# expLoRaBLE_Thing_Plus.net
KiCad netlist of a schematic drawn in EAGLE
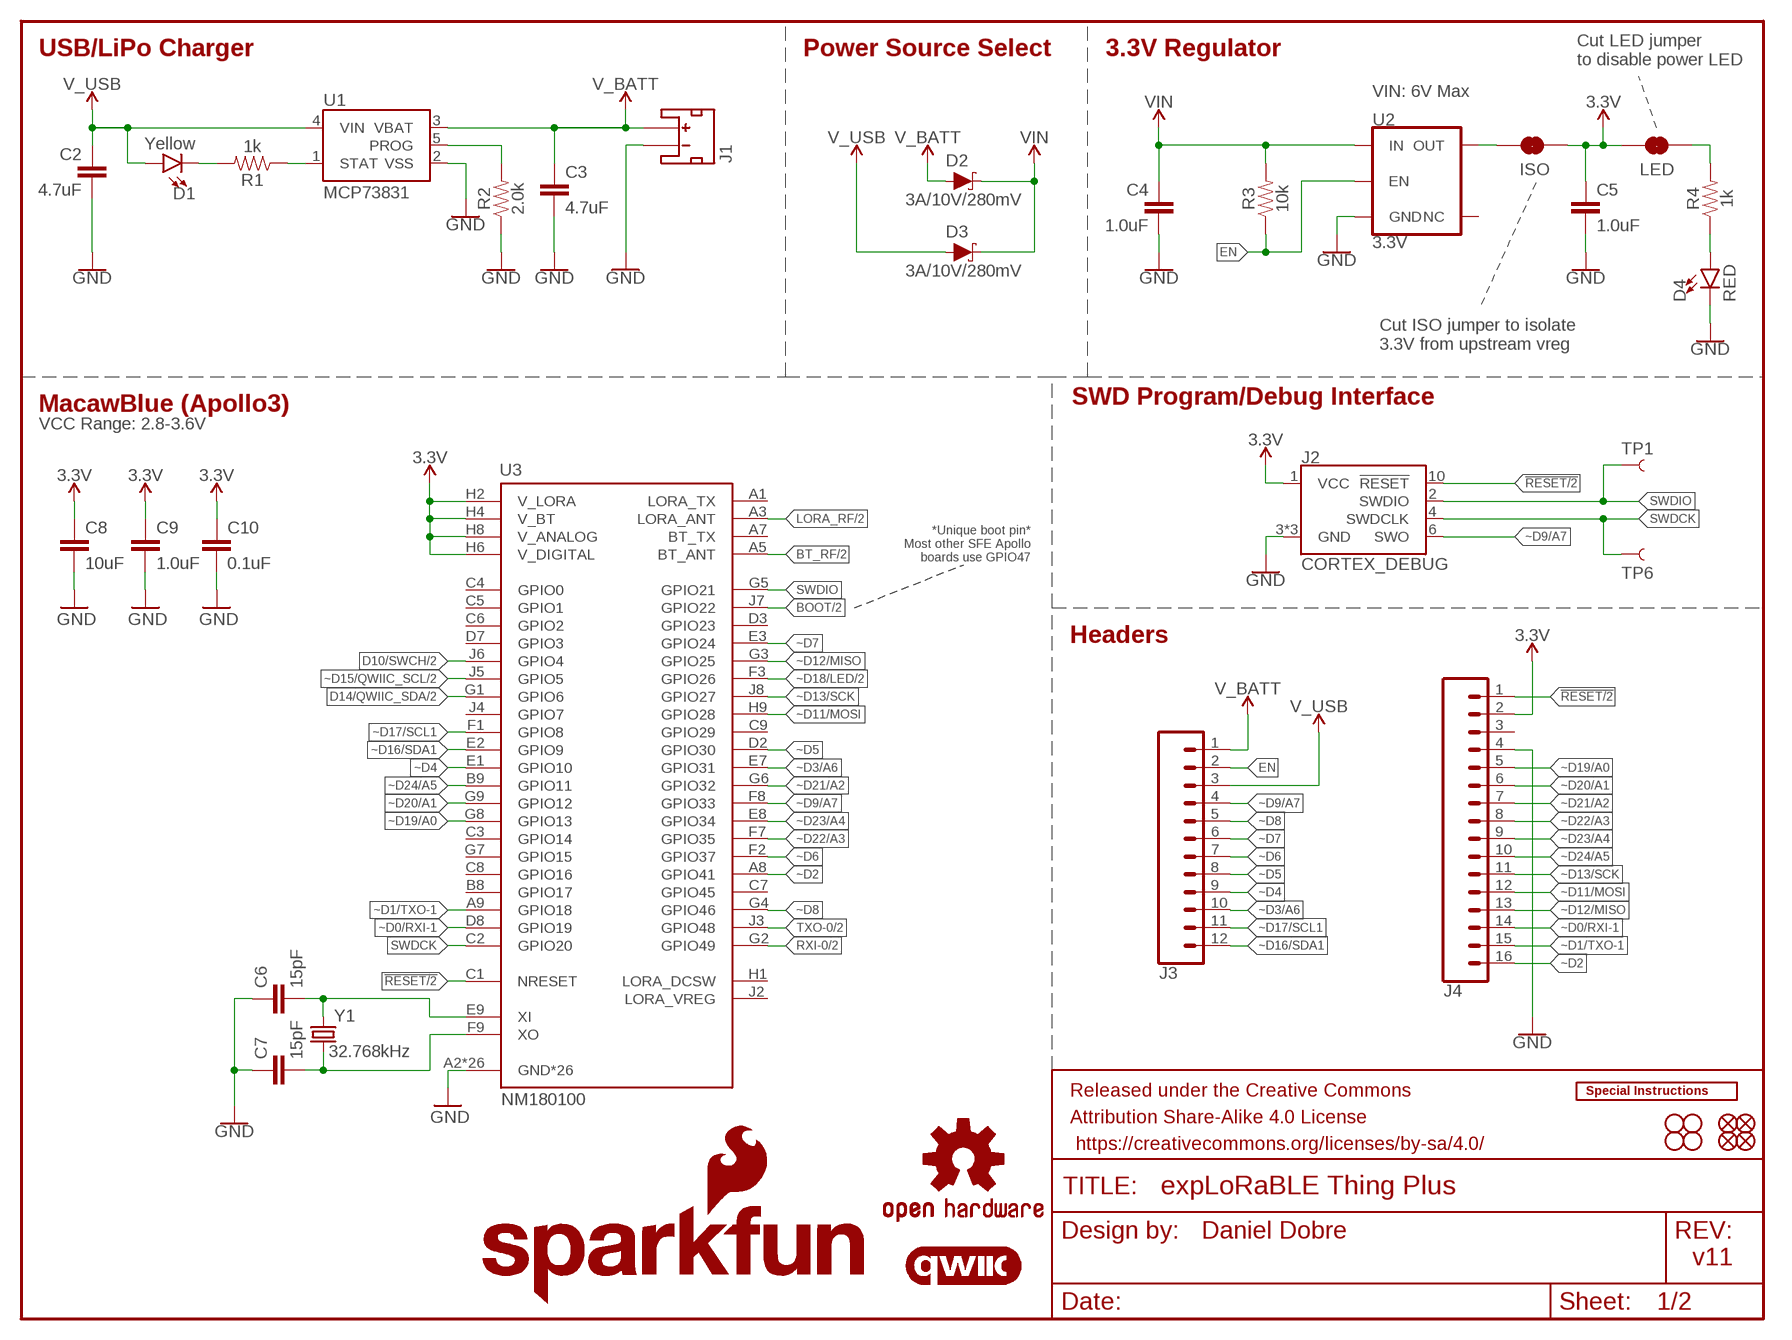
[diagram p0: schematic, sheet 1]
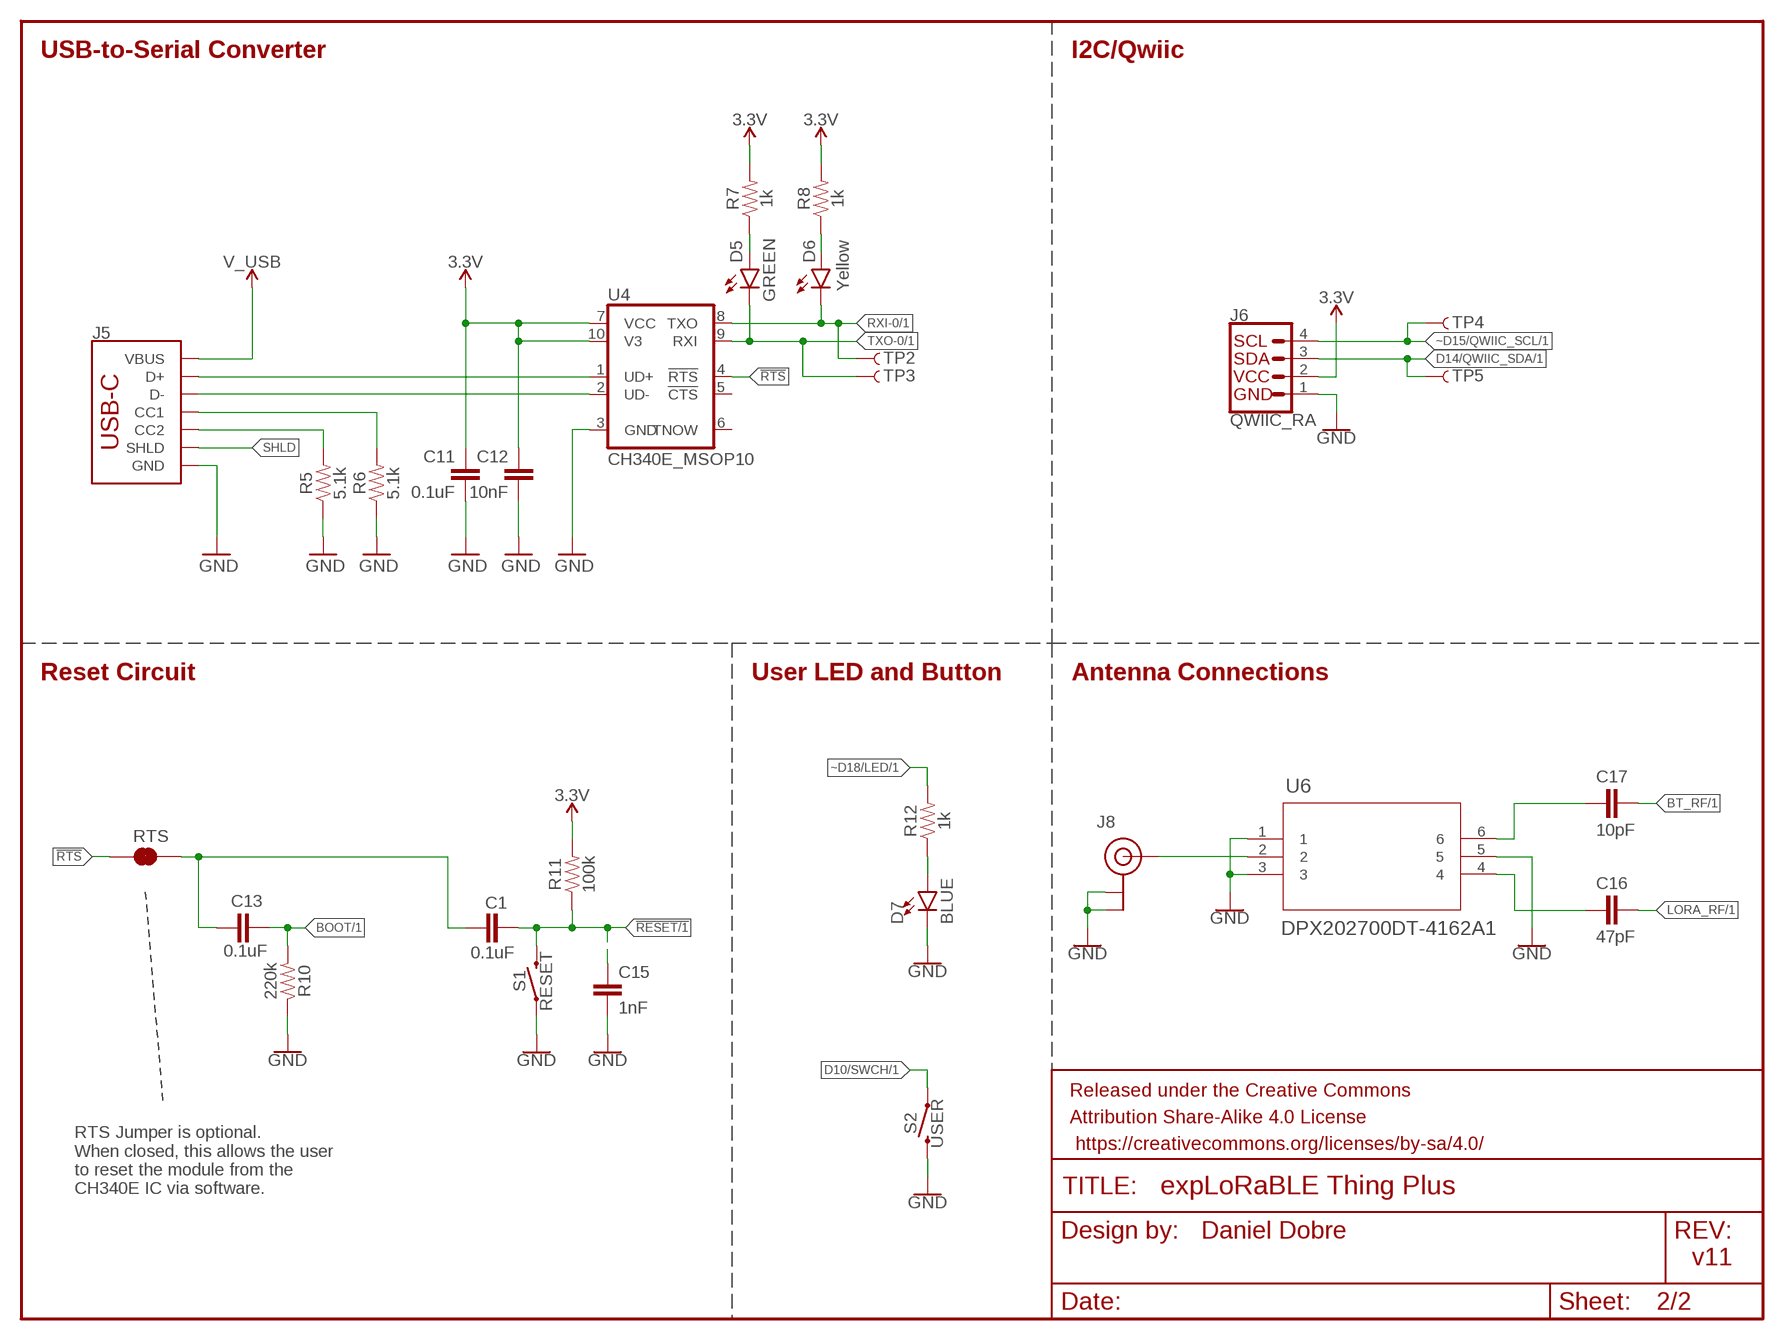
[diagram p1: schematic, sheet 2]

(export (version "E")
  (design (tool "Eeschema 10.0.6"))
  (components
    (comp (ref "C1")
      (value "0.1uF")
      (footprint "eagle-import:0603")
      (libsource (lib "eagle-import") (part "SparkFun-Capacitors_510_0.1UF-0603-25V-(+80/-20%)"))
    )
    (comp (ref "C11")
      (value "0.1uF")
      (footprint "eagle-import:0603")
      (libsource (lib "eagle-import") (part "SparkFun-Capacitors_23925113_0.1UF-0603-25V-(+80/-20%)"))
    )
    (comp (ref "C12")
      (value "10nF")
      (footprint "eagle-import:0603")
      (libsource (lib "eagle-import") (part "10NF-0603-50V-10%"))
    )
    (comp (ref "C13")
      (value "0.1uF")
      (footprint "eagle-import:0603")
      (libsource (lib "eagle-import") (part "0.1UF-0603-25V-(+80/-20%)"))
    )
    (comp (ref "C15")
      (value "1nF")
      (footprint "eagle-import:0603")
      (libsource (lib "eagle-import") (part "1.0NF/1000PF-0603-50V-10%"))
    )
    (comp (ref "C16")
      (value "47pF")
      (footprint "eagle-import:0603")
      (libsource (lib "eagle-import") (part "47PF-0603-50V-5%"))
    )
    (comp (ref "C17")
      (value "10pF")
      (footprint "eagle-import:0603")
      (libsource (lib "eagle-import") (part "10PF-0603-50V-5%"))
    )
    (comp (ref "D5")
      (value "GREEN")
      (footprint "eagle-import:LED-0603")
      (libsource (lib "eagle-import") (part "LED-GREEN0603"))
    )
    (comp (ref "D6")
      (value "Yellow")
      (footprint "eagle-import:LED-0603")
      (libsource (lib "eagle-import") (part "LED-YELLOW0603"))
    )
    (comp (ref "D7")
      (value "BLUE")
      (footprint "eagle-import:LED-0603")
      (libsource (lib "eagle-import") (part "LED-BLUE0603"))
    )
    (comp (ref "FRAME2")
      (value "FRAME-LETTERNO_PACKAGE")
      (footprint "eagle-import:DUMMY")
      (fields (field (name "DESIGNER") "Nobody"))
      (libsource (lib "eagle-import") (part "FRAME-LETTERNO_PACKAGE"))
    )
    (comp (ref "J5")
      (value "USB Female Type C Connector")
      (footprint "eagle-import:USB-C-16P-4LAYER-ISOLATED")
      (libsource (lib "eagle-import") (part "USB_C_4-LAYER-ISOLATED"))
    )
    (comp (ref "J6")
      (value "QWIIC_RA")
      (footprint "eagle-import:JST04_1MM_RA")
      (libsource (lib "eagle-import") (part "QWIIC_CONNECTORJS-1MM"))
    )
    (comp (ref "J8")
      (value "U.FL")
      (footprint "eagle-import:U.FL")
      (libsource (lib "eagle-import") (part "U.FL"))
    )
    (comp (ref "R5")
      (value "5.1k")
      (footprint "eagle-import:0603")
      (libsource (lib "eagle-import") (part "5.1KOHM5.1KOHM-0603-1/10W-1%"))
    )
    (comp (ref "R6")
      (value "5.1k")
      (footprint "eagle-import:0603")
      (libsource (lib "eagle-import") (part "5.1KOHM5.1KOHM-0603-1/10W-1%"))
    )
    (comp (ref "R7")
      (value "1k")
      (footprint "eagle-import:0603")
      (libsource (lib "eagle-import") (part "1KOHM-0603-1/10W-1%"))
    )
    (comp (ref "R8")
      (value "1k")
      (footprint "eagle-import:0603")
      (libsource (lib "eagle-import") (part "1KOHM-0603-1/10W-1%"))
    )
    (comp (ref "R10")
      (value "220k")
      (footprint "eagle-import:0603")
      (libsource (lib "eagle-import") (part "220KOHM-0603-1/10W-1%"))
    )
    (comp (ref "R11")
      (value "100k")
      (footprint "eagle-import:0603")
      (libsource (lib "eagle-import") (part "100KOHM-0603-1/10W-1%"))
    )
    (comp (ref "R12")
      (value "1k")
      (footprint "eagle-import:0603")
      (libsource (lib "eagle-import") (part "1KOHM-0603-1/10W-1%"))
    )
    (comp (ref "RTS")
      (value "JUMPER-SMT_2_NC_TRACE_SILK")
      (footprint "eagle-import:SMT-JUMPER_2_NC_TRACE_SILK")
      (libsource (lib "eagle-import") (part "JUMPER-SMT_2_NC_TRACE_SILK"))
    )
    (comp (ref "S1")
      (value "RESET")
      (footprint "eagle-import:TACTILE_SWITCH_SMD_4.6X2.8MM")
      (libsource (lib "eagle-import") (part "MOMENTARY-SWITCH-SPST-SMD-4.6X2.8MM"))
    )
    (comp (ref "S2")
      (value "USER")
      (footprint "eagle-import:TACTILE_SWITCH_SMD_4.6X2.8MM")
      (libsource (lib "eagle-import") (part "MOMENTARY-SWITCH-SPST-SMD-4.6X2.8MM"))
    )
    (comp (ref "TP2")
      (value "TEST-POINTTP_15TH_THRU")
      (footprint "eagle-import:TP_15TH")
      (libsource (lib "eagle-import") (part "TEST-POINTTP_15TH_THRU"))
    )
    (comp (ref "TP3")
      (value "TEST-POINTTP_15TH_THRU")
      (footprint "eagle-import:TP_15TH")
      (libsource (lib "eagle-import") (part "TEST-POINTTP_15TH_THRU"))
    )
    (comp (ref "TP4")
      (value "TEST-POINTTP_15TH_THRU")
      (footprint "eagle-import:TP_15TH")
      (libsource (lib "eagle-import") (part "TEST-POINTTP_15TH_THRU"))
    )
    (comp (ref "TP5")
      (value "TEST-POINTTP_15TH_THRU")
      (footprint "eagle-import:TP_15TH")
      (libsource (lib "eagle-import") (part "TEST-POINTTP_15TH_THRU"))
    )
    (comp (ref "U4")
      (value "CH340E_MSOP10")
      (footprint "eagle-import:MSOP10")
      (libsource (lib "eagle-import") (part "CH340E_MSOP10"))
    )
    (comp (ref "U6")
      (value "DPX202700DT-4162A1")
      (footprint "eagle-import:RF_4060A1_TDK")
      (fields (field (name "COPYRIGHT") "Copyright (C) 2018 Accelerated Designs. All rights reserved"))
      (libsource (lib "eagle-import") (part "DPX202700DT-4162A1"))
    )
    (comp (ref "C2")
      (value "4.7uF")
      (footprint "eagle-import:0603")
      (libsource (lib "eagle-import") (part "4.7UF-0603-6.3V-(10%)"))
    )
    (comp (ref "C3")
      (value "4.7uF")
      (footprint "eagle-import:0603")
      (libsource (lib "eagle-import") (part "4.7UF-0603-6.3V-(10%)"))
    )
    (comp (ref "C4")
      (value "1.0uF")
      (footprint "eagle-import:0603")
      (libsource (lib "eagle-import") (part "1.0UF-0603-16V-10%"))
    )
    (comp (ref "C5")
      (value "1.0uF")
      (footprint "eagle-import:0603")
      (libsource (lib "eagle-import") (part "1.0UF-0603-16V-10%"))
    )
    (comp (ref "C6")
      (value "15pF")
      (footprint "eagle-import:0603")
      (libsource (lib "eagle-import") (part "15PF-0603-50V-5%"))
    )
    (comp (ref "C7")
      (value "15pF")
      (footprint "eagle-import:0603")
      (libsource (lib "eagle-import") (part "15PF-0603-50V-5%"))
    )
    (comp (ref "C8")
      (value "10uF")
      (footprint "eagle-import:0603")
      (libsource (lib "eagle-import") (part "10UF-0603-6.3V-20%"))
    )
    (comp (ref "C9")
      (value "1.0uF")
      (footprint "eagle-import:0603")
      (libsource (lib "eagle-import") (part "1.0UF-0603-16V-10%"))
    )
    (comp (ref "C10")
      (value "0.1uF")
      (footprint "eagle-import:0603")
      (libsource (lib "eagle-import") (part "SparkFun-Capacitors_23925113_0.1UF-0603-25V-(+80/-20%)"))
    )
    (comp (ref "D1")
      (value "Yellow")
      (footprint "eagle-import:LED-0603")
      (libsource (lib "eagle-import") (part "LED-YELLOW0603"))
    )
    (comp (ref "D2")
      (value "3A/10V/280mV")
      (footprint "eagle-import:SOD-323")
      (libsource (lib "eagle-import") (part "DIODE-SCHOTTKY-BAT60A"))
    )
    (comp (ref "D3")
      (value "3A/10V/280mV")
      (footprint "eagle-import:SOD-323")
      (libsource (lib "eagle-import") (part "DIODE-SCHOTTKY-BAT60A"))
    )
    (comp (ref "D4")
      (value "RED")
      (footprint "eagle-import:LED-0603")
      (libsource (lib "eagle-import") (part "LED-RED0603"))
    )
    (comp (ref "FD1")
      (value "FIDUCIALUFIDUCIAL")
      (footprint "eagle-import:FIDUCIAL-MICRO")
      (libsource (lib "eagle-import") (part "FIDUCIALUFIDUCIAL"))
    )
    (comp (ref "FD2")
      (value "FIDUCIALUFIDUCIAL")
      (footprint "eagle-import:FIDUCIAL-MICRO")
      (libsource (lib "eagle-import") (part "FIDUCIALUFIDUCIAL"))
    )
    (comp (ref "FD3")
      (value "FIDUCIALUFIDUCIAL")
      (footprint "eagle-import:FIDUCIAL-MICRO")
      (libsource (lib "eagle-import") (part "FIDUCIALUFIDUCIAL"))
    )
    (comp (ref "FD4")
      (value "FIDUCIALUFIDUCIAL")
      (footprint "eagle-import:FIDUCIAL-MICRO")
      (libsource (lib "eagle-import") (part "FIDUCIALUFIDUCIAL"))
    )
    (comp (ref "FRAME1")
      (value "FRAME-LETTER")
      (footprint "eagle-import:CREATIVE_COMMONS")
      (libsource (lib "eagle-import") (part "FRAME-LETTER"))
    )
    (comp (ref "H1")
      (value "STAND-OFF")
      (footprint "eagle-import:STAND-OFF")
      (libsource (lib "eagle-import") (part "STAND-OFF"))
    )
    (comp (ref "H2")
      (value "STAND-OFF")
      (footprint "eagle-import:STAND-OFF")
      (libsource (lib "eagle-import") (part "STAND-OFF"))
    )
    (comp (ref "H3")
      (value "STAND-OFF")
      (footprint "eagle-import:STAND-OFF")
      (libsource (lib "eagle-import") (part "STAND-OFF"))
    )
    (comp (ref "H4")
      (value "STAND-OFF")
      (footprint "eagle-import:STAND-OFF")
      (libsource (lib "eagle-import") (part "STAND-OFF"))
    )
    (comp (ref "ISO")
      (value "JUMPER-SMT_2_NC_TRACE_SILK")
      (footprint "eagle-import:SMT-JUMPER_2_NC_TRACE_SILK")
      (libsource (lib "eagle-import") (part "JUMPER-SMT_2_NC_TRACE_SILK"))
    )
    (comp (ref "J1")
      (value "JST_2MM_MALE")
      (footprint "eagle-import:JST-2-SMD")
      (libsource (lib "eagle-import") (part "JST_2MM_MALE"))
    )
    (comp (ref "J2")
      (value "CORTEX_DEBUG")
      (footprint "eagle-import:2X5-PTH-1.27MM-NO_SILK")
      (libsource (lib "eagle-import") (part "CORTEX_DEBUG_MINIMUM_PTH_NS"))
    )
    (comp (ref "J3")
      (value "CONN_12SM_SQ_NO_SILK")
      (footprint "eagle-import:1X12_SM_SQ_NOSILK")
      (libsource (lib "eagle-import") (part "CONN_12SM_SQ_NO_SILK"))
    )
    (comp (ref "J4")
      (value "CONN_161X16_SM_SQ_NOSILK")
      (footprint "eagle-import:1X16_SM_SQ_NOSILK")
      (libsource (lib "eagle-import") (part "CONN_161X16_SM_SQ_NOSILK"))
    )
    (comp (ref "LED")
      (value "JUMPER-SMT_2_NC_TRACE_SILK")
      (footprint "eagle-import:SMT-JUMPER_2_NC_TRACE_SILK")
      (libsource (lib "eagle-import") (part "JUMPER-SMT_2_NC_TRACE_SILK"))
    )
    (comp (ref "LOGO1")
      (value "OSHW-LOGOS")
      (footprint "eagle-import:OSHW-LOGO-S")
      (libsource (lib "eagle-import") (part "OSHW-LOGOS"))
    )
    (comp (ref "LOGO2")
      (value "QWIIC_LOGO_5MM")
      (footprint "eagle-import:QWIIC_5MM")
      (libsource (lib "eagle-import") (part "QWIIC_LOGO_5MM"))
    )
    (comp (ref "LOGO3")
      (value "SFE_LOGO_NAME_FLAME.1_INCH")
      (footprint "eagle-import:SFE_LOGO_NAME_FLAME_.1")
      (libsource (lib "eagle-import") (part "SFE_LOGO_NAME_FLAME.1_INCH"))
    )
    (comp (ref "LOGO4")
      (value "SPECIAL_INSTRUCTIONS-ORDERING")
      (footprint "eagle-import:ORDERING_INSTRUCTIONS")
      (libsource (lib "eagle-import") (part "SPECIAL_INSTRUCTIONS-ORDERING"))
    )
    (comp (ref "R1")
      (value "1k")
      (footprint "eagle-import:0603")
      (libsource (lib "eagle-import") (part "1KOHM-0603-1/10W-1%"))
    )
    (comp (ref "R2")
      (value "2.0k")
      (footprint "eagle-import:0603")
      (libsource (lib "eagle-import") (part "2.0KOHM-0603-1/10W-5%"))
    )
    (comp (ref "R3")
      (value "10k")
      (footprint "eagle-import:0603")
      (libsource (lib "eagle-import") (part "10KOHM-0603-1/10W-1%"))
    )
    (comp (ref "R4")
      (value "1k")
      (footprint "eagle-import:0603")
      (libsource (lib "eagle-import") (part "1KOHM-0603-1/10W-1%"))
    )
    (comp (ref "TP1")
      (value "TEST-POINTTP_15TH_THRU")
      (footprint "eagle-import:TP_15TH")
      (libsource (lib "eagle-import") (part "SparkFun-Connectors_513_TEST-POINTTP_15TH_THRU"))
    )
    (comp (ref "TP6")
      (value "TEST-POINTTP_15TH_THRU")
      (footprint "eagle-import:TP_15TH")
      (libsource (lib "eagle-import") (part "SparkFun-Connectors_513_TEST-POINTTP_15TH_THRU"))
    )
    (comp (ref "U1")
      (value "MCP73831")
      (footprint "eagle-import:SOT23-5")
      (libsource (lib "eagle-import") (part "MCP73831"))
    )
    (comp (ref "U2")
      (value "3.3V")
      (footprint "eagle-import:SOT23-5")
      (libsource (lib "eagle-import") (part "V_REG_AP2112K-3.3V"))
    )
    (comp (ref "U3")
      (value "NM180100")
      (footprint "eagle-import:LGA81")
      (libsource (lib "eagle-import") (part "NM180100"))
    )
    (comp (ref "Y1")
      (value "32.768kHz")
      (footprint "eagle-import:CRYSTAL-SMD-3.2X1.5MM")
      (libsource (lib "eagle-import") (part "CRYSTAL-32.768KHZSMD-3.2X1.5"))
    )
  )
  (nets
    (net (code "1") (name "3.3V") (class "Default")
      (node (ref "C10") (pin "1") (pinfunction "1_1") (pintype "passive"))
      (node (ref "C11") (pin "1") (pinfunction "1_1") (pintype "passive"))
      (node (ref "C12") (pin "1") (pinfunction "1_1") (pintype "passive"))
      (node (ref "C5") (pin "1") (pinfunction "1_1") (pintype "passive"))
      (node (ref "C8") (pin "1") (pinfunction "1_1") (pintype "passive"))
      (node (ref "C9") (pin "1") (pinfunction "1_1") (pintype "passive"))
      (node (ref "ISO") (pin "1") (pinfunction "1_1") (pintype "passive"))
      (node (ref "J2") (pin "1") (pinfunction "VCC_1") (pintype "bidirectional"))
      (node (ref "J4") (pin "2") (pinfunction "2_2") (pintype "passive"))
      (node (ref "J6") (pin "2") (pinfunction "2_2") (pintype "power_in"))
      (node (ref "LED") (pin "2") (pinfunction "2_2") (pintype "passive"))
      (node (ref "R11") (pin "2") (pinfunction "2_2") (pintype "passive"))
      (node (ref "R7") (pin "2") (pinfunction "2_2") (pintype "passive"))
      (node (ref "R8") (pin "2") (pinfunction "2_2") (pintype "passive"))
      (node (ref "U3") (pin "H2") (pinfunction "V_LORA_H2") (pintype "bidirectional"))
      (node (ref "U3") (pin "H4") (pinfunction "V_BT_H4") (pintype "bidirectional"))
      (node (ref "U3") (pin "H6") (pinfunction "V_DIGITAL_H6") (pintype "bidirectional"))
      (node (ref "U3") (pin "H8") (pinfunction "V_ANALOG_H8") (pintype "bidirectional"))
      (node (ref "U4") (pin "10") (pinfunction "V3_10") (pintype "bidirectional"))
      (node (ref "U4") (pin "7") (pinfunction "VCC_7") (pintype "bidirectional"))
    )
    (net (code "2") (name "BOOT") (class "Default")
      (node (ref "C13") (pin "2") (pinfunction "2_2") (pintype "passive"))
      (node (ref "R10") (pin "2") (pinfunction "2_2") (pintype "passive"))
      (node (ref "U3") (pin "J7") (pinfunction "GPIO22_J7") (pintype "bidirectional"))
    )
    (net (code "3") (name "BT_RF") (class "Default")
      (node (ref "C17") (pin "1") (pinfunction "1_1") (pintype "passive"))
      (node (ref "U3") (pin "A5") (pinfunction "BT_ANT_A5") (pintype "bidirectional"))
    )
    (net (code "4") (name "D10{slash}SWCH") (class "Default")
      (node (ref "S2") (pin "1") (pinfunction "1_1") (pintype "passive"))
      (node (ref "S2") (pin "2") (pinfunction "1_2") (pintype "passive"))
      (node (ref "U3") (pin "J6") (pinfunction "GPIO4_J6") (pintype "bidirectional"))
    )
    (net (code "5") (name "D14{slash}QWIIC_SDA") (class "Default")
      (node (ref "J6") (pin "3") (pinfunction "3_3") (pintype "passive"))
      (node (ref "TP5") (pin "P$1") (pinfunction "1_P$1") (pintype "bidirectional"))
      (node (ref "U3") (pin "G1") (pinfunction "GPIO6_G1") (pintype "bidirectional"))
    )
    (net (code "6") (name "EN") (class "Default")
      (node (ref "J3") (pin "2") (pinfunction "2_2") (pintype "passive"))
      (node (ref "R3") (pin "1") (pinfunction "1_1") (pintype "passive"))
      (node (ref "U2") (pin "3") (pinfunction "EN_3") (pintype "input"))
    )
    (net (code "7") (name "GND") (class "Default")
      (node (ref "C10") (pin "2") (pinfunction "2_2") (pintype "passive"))
      (node (ref "C11") (pin "2") (pinfunction "2_2") (pintype "passive"))
      (node (ref "C12") (pin "2") (pinfunction "2_2") (pintype "passive"))
      (node (ref "C15") (pin "2") (pinfunction "2_2") (pintype "passive"))
      (node (ref "C2") (pin "2") (pinfunction "2_2") (pintype "passive"))
      (node (ref "C3") (pin "2") (pinfunction "2_2") (pintype "passive"))
      (node (ref "C4") (pin "2") (pinfunction "2_2") (pintype "passive"))
      (node (ref "C5") (pin "2") (pinfunction "2_2") (pintype "passive"))
      (node (ref "C6") (pin "1") (pinfunction "1_1") (pintype "passive"))
      (node (ref "C7") (pin "1") (pinfunction "1_1") (pintype "passive"))
      (node (ref "C8") (pin "2") (pinfunction "2_2") (pintype "passive"))
      (node (ref "C9") (pin "2") (pinfunction "2_2") (pintype "passive"))
      (node (ref "D4") (pin "C") (pinfunction "C_C") (pintype "passive"))
      (node (ref "D7") (pin "C") (pinfunction "C_C") (pintype "passive"))
      (node (ref "J1") (pin "1") (pinfunction "-_1") (pintype "bidirectional"))
      (node (ref "J2") (pin "3") (pinfunction "GND_3") (pintype "bidirectional"))
      (node (ref "J2") (pin "5") (pinfunction "GND_5") (pintype "bidirectional"))
      (node (ref "J2") (pin "9") (pinfunction "GND_9") (pintype "bidirectional"))
      (node (ref "J4") (pin "4") (pinfunction "4_4") (pintype "passive"))
      (node (ref "J5") (pin "GND") (pinfunction "GND_GND") (pintype "bidirectional"))
      (node (ref "J5") (pin "GND2") (pinfunction "GND_GND2") (pintype "bidirectional"))
      (node (ref "J6") (pin "1") (pinfunction "1_1") (pintype "power_in"))
      (node (ref "J8") (pin "1") (pinfunction "GND_1") (pintype "bidirectional"))
      (node (ref "J8") (pin "2") (pinfunction "GND_2") (pintype "bidirectional"))
      (node (ref "R10") (pin "1") (pinfunction "1_1") (pintype "passive"))
      (node (ref "R2") (pin "1") (pinfunction "1_1") (pintype "passive"))
      (node (ref "R5") (pin "1") (pinfunction "1_1") (pintype "passive"))
      (node (ref "R6") (pin "1") (pinfunction "1_1") (pintype "passive"))
      (node (ref "S1") (pin "1") (pinfunction "1_1") (pintype "passive"))
      (node (ref "S1") (pin "2") (pinfunction "1_2") (pintype "passive"))
      (node (ref "S2") (pin "3") (pinfunction "2_3") (pintype "passive"))
      (node (ref "S2") (pin "4") (pinfunction "2_4") (pintype "passive"))
      (node (ref "U1") (pin "2") (pinfunction "VSS_2") (pintype "power_in"))
      (node (ref "U2") (pin "2") (pinfunction "GND_2") (pintype "input"))
      (node (ref "U3") (pin "A2") (pinfunction "GND*26_A2") (pintype "bidirectional"))
      (node (ref "U3") (pin "A4") (pinfunction "GND*26_A4") (pintype "bidirectional"))
      (node (ref "U3") (pin "A6") (pinfunction "GND*26_A6") (pintype "bidirectional"))
      (node (ref "U3") (pin "B1") (pinfunction "GND*26_B1") (pintype "bidirectional"))
      (node (ref "U3") (pin "B2") (pinfunction "GND*26_B2") (pintype "bidirectional"))
      (node (ref "U3") (pin "B3") (pinfunction "GND*26_B3") (pintype "bidirectional"))
      (node (ref "U3") (pin "B4") (pinfunction "GND*26_B4") (pintype "bidirectional"))
      (node (ref "U3") (pin "B5") (pinfunction "GND*26_B5") (pintype "bidirectional"))
      (node (ref "U3") (pin "B6") (pinfunction "GND*26_B6") (pintype "bidirectional"))
      (node (ref "U3") (pin "B7") (pinfunction "GND*26_B7") (pintype "bidirectional"))
      (node (ref "U3") (pin "D1") (pinfunction "GND*26_D1") (pintype "bidirectional"))
      (node (ref "U3") (pin "D4") (pinfunction "GND*26_D4") (pintype "bidirectional"))
      (node (ref "U3") (pin "D5") (pinfunction "GND*26_D5") (pintype "bidirectional"))
      (node (ref "U3") (pin "D6") (pinfunction "GND*26_D6") (pintype "bidirectional"))
      (node (ref "U3") (pin "D9") (pinfunction "GND*26_D9") (pintype "bidirectional"))
      (node (ref "U3") (pin "E4") (pinfunction "GND*26_E4") (pintype "bidirectional"))
      (node (ref "U3") (pin "E5") (pinfunction "GND*26_E5") (pintype "bidirectional"))
      (node (ref "U3") (pin "E6") (pinfunction "GND*26_E6") (pintype "bidirectional"))
      (node (ref "U3") (pin "F4") (pinfunction "GND*26_F4") (pintype "bidirectional"))
      (node (ref "U3") (pin "F5") (pinfunction "GND*26_F5") (pintype "bidirectional"))
      (node (ref "U3") (pin "F6") (pinfunction "GND*26_F6") (pintype "bidirectional"))
      (node (ref "U3") (pin "H3") (pinfunction "GND*26_H3") (pintype "bidirectional"))
      (node (ref "U3") (pin "H5") (pinfunction "GND*26_H5") (pintype "bidirectional"))
      (node (ref "U3") (pin "H7") (pinfunction "GND*26_H7") (pintype "bidirectional"))
      (node (ref "U3") (pin "J1") (pinfunction "GND*26_J1") (pintype "bidirectional"))
      (node (ref "U3") (pin "J9") (pinfunction "GND*26_J9") (pintype "bidirectional"))
      (node (ref "U4") (pin "3") (pinfunction "GND_3") (pintype "bidirectional"))
      (node (ref "U6") (pin "1") (pinfunction "1_1") (pintype "passive"))
      (node (ref "U6") (pin "3") (pinfunction "3_3") (pintype "passive"))
      (node (ref "U6") (pin "5") (pinfunction "5_5") (pintype "passive"))
    )
    (net (code "8") (name "LORA_RF") (class "Default")
      (node (ref "C16") (pin "1") (pinfunction "1_1") (pintype "passive"))
      (node (ref "U3") (pin "A3") (pinfunction "LORA_ANT_A3") (pintype "bidirectional"))
    )
    (net (code "9") (name "Net-(C1-Pad1)") (class "Default")
      (node (ref "C1") (pin "1") (pinfunction "1_1") (pintype "passive"))
      (node (ref "C13") (pin "1") (pinfunction "1_1") (pintype "passive"))
      (node (ref "RTS") (pin "2") (pinfunction "2_2") (pintype "passive"))
    )
    (net (code "10") (name "Net-(C16-Pad2)") (class "Default")
      (node (ref "C16") (pin "2") (pinfunction "2_2") (pintype "passive"))
      (node (ref "U6") (pin "4") (pinfunction "4_4") (pintype "passive"))
    )
    (net (code "11") (name "Net-(C17-Pad2)") (class "Default")
      (node (ref "C17") (pin "2") (pinfunction "2_2") (pintype "passive"))
      (node (ref "U6") (pin "6") (pinfunction "6_6") (pintype "passive"))
    )
    (net (code "12") (name "Net-(D1-PadC)") (class "Default")
      (node (ref "D1") (pin "C") (pinfunction "C_C") (pintype "passive"))
      (node (ref "R1") (pin "2") (pinfunction "2_2") (pintype "passive"))
    )
    (net (code "13") (name "Net-(D4-PadA)") (class "Default")
      (node (ref "D4") (pin "A") (pinfunction "A_A") (pintype "passive"))
      (node (ref "R4") (pin "1") (pinfunction "1_1") (pintype "passive"))
    )
    (net (code "14") (name "Net-(D5-PadA)") (class "Default")
      (node (ref "D5") (pin "A") (pinfunction "A_A") (pintype "passive"))
      (node (ref "R7") (pin "1") (pinfunction "1_1") (pintype "passive"))
    )
    (net (code "15") (name "Net-(D6-PadA)") (class "Default")
      (node (ref "D6") (pin "A") (pinfunction "A_A") (pintype "passive"))
      (node (ref "R8") (pin "1") (pinfunction "1_1") (pintype "passive"))
    )
    (net (code "16") (name "Net-(D7-PadA)") (class "Default")
      (node (ref "D7") (pin "A") (pinfunction "A_A") (pintype "passive"))
      (node (ref "R12") (pin "1") (pinfunction "1_1") (pintype "passive"))
    )
    (net (code "17") (name "Net-(J5-CC1)") (class "Default")
      (node (ref "J5") (pin "A5") (pinfunction "CC1_A5") (pintype "bidirectional"))
      (node (ref "R6") (pin "2") (pinfunction "2_2") (pintype "passive"))
    )
    (net (code "18") (name "Net-(J5-CC2)") (class "Default")
      (node (ref "J5") (pin "B5") (pinfunction "CC2_B5") (pintype "bidirectional"))
      (node (ref "R5") (pin "2") (pinfunction "2_2") (pintype "passive"))
    )
    (net (code "19") (name "Net-(J8-SIGNAL)") (class "Default")
      (node (ref "J8") (pin "FEED") (pinfunction "SIGNAL_FEED") (pintype "bidirectional"))
      (node (ref "U6") (pin "2") (pinfunction "2_2") (pintype "passive"))
    )
    (net (code "20") (name "Net-(LED-Pad1)") (class "Default")
      (node (ref "LED") (pin "1") (pinfunction "1_1") (pintype "passive"))
      (node (ref "R4") (pin "2") (pinfunction "2_2") (pintype "passive"))
    )
    (net (code "21") (name "Net-(U1-PROG)") (class "Default")
      (node (ref "R2") (pin "2") (pinfunction "2_2") (pintype "passive"))
      (node (ref "U1") (pin "5") (pinfunction "PROG_5") (pintype "input"))
    )
    (net (code "22") (name "Net-(U1-STAT)") (class "Default")
      (node (ref "R1") (pin "1") (pinfunction "1_1") (pintype "passive"))
      (node (ref "U1") (pin "1") (pinfunction "STAT_1") (pintype "output"))
    )
    (net (code "23") (name "Net-(U2-OUT)") (class "Default")
      (node (ref "ISO") (pin "2") (pinfunction "2_2") (pintype "passive"))
      (node (ref "U2") (pin "5") (pinfunction "OUT_5") (pintype "passive"))
    )
    (net (code "24") (name "Net-(U3-XI)") (class "Default")
      (node (ref "C6") (pin "2") (pinfunction "2_2") (pintype "passive"))
      (node (ref "U3") (pin "E9") (pinfunction "XI_E9") (pintype "bidirectional"))
      (node (ref "Y1") (pin "P$1") (pinfunction "1_P$1") (pintype "passive"))
    )
    (net (code "25") (name "Net-(U3-XO)") (class "Default")
      (node (ref "C7") (pin "2") (pinfunction "2_2") (pintype "passive"))
      (node (ref "U3") (pin "F9") (pinfunction "XO_F9") (pintype "bidirectional"))
      (node (ref "Y1") (pin "P$2") (pinfunction "2_P$2") (pintype "passive"))
    )
    (net (code "26") (name "Net-(U4-UD+)") (class "Default")
      (node (ref "J5") (pin "A6") (pinfunction "D+_A6") (pintype "bidirectional"))
      (node (ref "J5") (pin "B6") (pinfunction "D+_B6") (pintype "bidirectional"))
      (node (ref "U4") (pin "1") (pinfunction "UD+_1") (pintype "bidirectional"))
    )
    (net (code "27") (name "Net-(U4-UD-)") (class "Default")
      (node (ref "J5") (pin "A7") (pinfunction "D-_A7") (pintype "bidirectional"))
      (node (ref "J5") (pin "B7") (pinfunction "D-_B7") (pintype "bidirectional"))
      (node (ref "U4") (pin "2") (pinfunction "UD-_2") (pintype "bidirectional"))
    )
    (net (code "28") (name "RXI-0") (class "Default")
      (node (ref "D6") (pin "C") (pinfunction "C_C") (pintype "passive"))
      (node (ref "TP2") (pin "P$1") (pinfunction "1_P$1") (pintype "bidirectional"))
      (node (ref "U3") (pin "G2") (pinfunction "GPIO49_G2") (pintype "bidirectional"))
      (node (ref "U4") (pin "8") (pinfunction "TXO_8") (pintype "bidirectional"))
    )
    (net (code "29") (name "SHLD") (class "Default")
      (node (ref "J5") (pin "SHLD1") (pinfunction "SHLD_SHLD1") (pintype "bidirectional"))
      (node (ref "J5") (pin "SHLD2") (pinfunction "SHLD_SHLD2") (pintype "bidirectional"))
      (node (ref "J5") (pin "SHLD3") (pinfunction "SHLD_SHLD3") (pintype "bidirectional"))
      (node (ref "J5") (pin "SHLD4") (pinfunction "SHLD_SHLD4") (pintype "bidirectional"))
      (node (ref "J5") (pin "SHLD5") (pinfunction "SHLD_SHLD5") (pintype "bidirectional"))
      (node (ref "J5") (pin "SHLD6") (pinfunction "SHLD_SHLD6") (pintype "bidirectional"))
      (node (ref "J5") (pin "SHLD7") (pinfunction "SHLD_SHLD7") (pintype "bidirectional"))
      (node (ref "J5") (pin "SHLD8") (pinfunction "SHLD_SHLD8") (pintype "bidirectional"))
    )
    (net (code "30") (name "SWDCK") (class "Default")
      (node (ref "J2") (pin "4") (pinfunction "SWDCLK_4") (pintype "bidirectional"))
      (node (ref "TP6") (pin "P$1") (pinfunction "1_P$1") (pintype "bidirectional"))
      (node (ref "U3") (pin "C2") (pinfunction "GPIO20_C2") (pintype "bidirectional"))
    )
    (net (code "31") (name "SWDIO") (class "Default")
      (node (ref "J2") (pin "2") (pinfunction "SWDIO_2") (pintype "bidirectional"))
      (node (ref "TP1") (pin "P$1") (pinfunction "1_P$1") (pintype "bidirectional"))
      (node (ref "U3") (pin "G5") (pinfunction "GPIO21_G5") (pintype "bidirectional"))
    )
    (net (code "32") (name "TXO-0") (class "Default")
      (node (ref "D5") (pin "C") (pinfunction "C_C") (pintype "passive"))
      (node (ref "TP3") (pin "P$1") (pinfunction "1_P$1") (pintype "bidirectional"))
      (node (ref "U3") (pin "J3") (pinfunction "GPIO48_J3") (pintype "bidirectional"))
      (node (ref "U4") (pin "9") (pinfunction "RXI_9") (pintype "bidirectional"))
    )
    (net (code "33") (name "VIN") (class "Default")
      (node (ref "C4") (pin "1") (pinfunction "1_1") (pintype "passive"))
      (node (ref "D2") (pin "C") (pinfunction "C_C") (pintype "passive"))
      (node (ref "D3") (pin "C") (pinfunction "C_C") (pintype "passive"))
      (node (ref "R3") (pin "2") (pinfunction "2_2") (pintype "passive"))
      (node (ref "U2") (pin "1") (pinfunction "IN_1") (pintype "input"))
    )
    (net (code "34") (name "V_BATT") (class "Default")
      (node (ref "C3") (pin "1") (pinfunction "1_1") (pintype "passive"))
      (node (ref "D2") (pin "A") (pinfunction "A_A") (pintype "passive"))
      (node (ref "J1") (pin "2") (pinfunction "+_2") (pintype "bidirectional"))
      (node (ref "J3") (pin "1") (pinfunction "1_1") (pintype "passive"))
      (node (ref "U1") (pin "3") (pinfunction "VBAT_3") (pintype "power_in"))
    )
    (net (code "35") (name "V_USB") (class "Default")
      (node (ref "C2") (pin "1") (pinfunction "1_1") (pintype "passive"))
      (node (ref "D1") (pin "A") (pinfunction "A_A") (pintype "passive"))
      (node (ref "D3") (pin "A") (pinfunction "A_A") (pintype "passive"))
      (node (ref "J3") (pin "3") (pinfunction "3_3") (pintype "passive"))
      (node (ref "J5") (pin "VBUS1") (pinfunction "VBUS_VBUS1") (pintype "bidirectional"))
      (node (ref "J5") (pin "VBUS2") (pinfunction "VBUS_VBUS2") (pintype "bidirectional"))
      (node (ref "U1") (pin "4") (pinfunction "VIN_4") (pintype "power_in"))
    )
    (net (code "36") (name "unconnected-(J1-PAD1-PadNC1)") (class "Default")
      (node (ref "J1") (pin "NC1") (pinfunction "PAD1_NC1") (pintype "bidirectional"))
    )
    (net (code "37") (name "unconnected-(J1-PAD2-PadNC2)") (class "Default")
      (node (ref "J1") (pin "NC2") (pinfunction "PAD2_NC2") (pintype "bidirectional"))
    )
    (net (code "38") (name "unconnected-(J4-Pad3)") (class "Default")
      (node (ref "J4") (pin "3") (pinfunction "3_3") (pintype "passive"))
    )
    (net (code "39") (name "unconnected-(U2-NC-Pad4)") (class "Default")
      (node (ref "U2") (pin "4") (pinfunction "NC_4") (pintype "no_connect"))
    )
    (net (code "40") (name "unconnected-(U3-BT_TX-PadA7)") (class "Default")
      (node (ref "U3") (pin "A7") (pinfunction "BT_TX_A7") (pintype "bidirectional"))
    )
    (net (code "41") (name "unconnected-(U3-GPIO0-PadC4)") (class "Default")
      (node (ref "U3") (pin "C4") (pinfunction "GPIO0_C4") (pintype "bidirectional"))
    )
    (net (code "42") (name "unconnected-(U3-GPIO1-PadC5)") (class "Default")
      (node (ref "U3") (pin "C5") (pinfunction "GPIO1_C5") (pintype "bidirectional"))
    )
    (net (code "43") (name "unconnected-(U3-GPIO2-PadC6)") (class "Default")
      (node (ref "U3") (pin "C6") (pinfunction "GPIO2_C6") (pintype "bidirectional"))
    )
    (net (code "44") (name "unconnected-(U3-GPIO3-PadD7)") (class "Default")
      (node (ref "U3") (pin "D7") (pinfunction "GPIO3_D7") (pintype "bidirectional"))
    )
    (net (code "45") (name "unconnected-(U3-GPIO7-PadJ4)") (class "Default")
      (node (ref "U3") (pin "J4") (pinfunction "GPIO7_J4") (pintype "bidirectional"))
    )
    (net (code "46") (name "unconnected-(U3-GPIO14-PadC3)") (class "Default")
      (node (ref "U3") (pin "C3") (pinfunction "GPIO14_C3") (pintype "bidirectional"))
    )
    (net (code "47") (name "unconnected-(U3-GPIO15-PadG7)") (class "Default")
      (node (ref "U3") (pin "G7") (pinfunction "GPIO15_G7") (pintype "bidirectional"))
    )
    (net (code "48") (name "unconnected-(U3-GPIO16-PadC8)") (class "Default")
      (node (ref "U3") (pin "C8") (pinfunction "GPIO16_C8") (pintype "bidirectional"))
    )
    (net (code "49") (name "unconnected-(U3-GPIO17-PadB8)") (class "Default")
      (node (ref "U3") (pin "B8") (pinfunction "GPIO17_B8") (pintype "bidirectional"))
    )
    (net (code "50") (name "unconnected-(U3-GPIO23-PadD3)") (class "Default")
      (node (ref "U3") (pin "D3") (pinfunction "GPIO23_D3") (pintype "bidirectional"))
    )
    (net (code "51") (name "unconnected-(U3-GPIO29-PadC9)") (class "Default")
      (node (ref "U3") (pin "C9") (pinfunction "GPIO29_C9") (pintype "bidirectional"))
    )
    (net (code "52") (name "unconnected-(U3-GPIO45-PadC7)") (class "Default")
      (node (ref "U3") (pin "C7") (pinfunction "GPIO45_C7") (pintype "bidirectional"))
    )
    (net (code "53") (name "unconnected-(U3-LORA_DCSW-PadH1)") (class "Default")
      (node (ref "U3") (pin "H1") (pinfunction "LORA_DCSW_H1") (pintype "bidirectional"))
    )
    (net (code "54") (name "unconnected-(U3-LORA_TX-PadA1)") (class "Default")
      (node (ref "U3") (pin "A1") (pinfunction "LORA_TX_A1") (pintype "bidirectional"))
    )
    (net (code "55") (name "unconnected-(U3-LORA_VREG-PadJ2)") (class "Default")
      (node (ref "U3") (pin "J2") (pinfunction "LORA_VREG_J2") (pintype "bidirectional"))
    )
    (net (code "56") (name "unconnected-(U4-TNOW-Pad6)") (class "Default")
      (node (ref "U4") (pin "6") (pinfunction "TNOW_6") (pintype "bidirectional"))
    )
    (net (code "57") (name "unconnected-(U4-~{CTS}-Pad5)") (class "Default")
      (node (ref "U4") (pin "5") (pinfunction "~{CTS}_5") (pintype "bidirectional"))
    )
    (net (code "58") (name "~{D0{slash}RXI-1}") (class "Default")
      (node (ref "J4") (pin "14") (pinfunction "14_14") (pintype "passive"))
      (node (ref "U3") (pin "D8") (pinfunction "GPIO19_D8") (pintype "bidirectional"))
    )
    (net (code "59") (name "~{D1{slash}TXO-1}") (class "Default")
      (node (ref "J4") (pin "15") (pinfunction "15_15") (pintype "passive"))
      (node (ref "U3") (pin "A9") (pinfunction "GPIO18_A9") (pintype "bidirectional"))
    )
    (net (code "60") (name "~{D2}") (class "Default")
      (node (ref "J4") (pin "16") (pinfunction "16_16") (pintype "passive"))
      (node (ref "U3") (pin "A8") (pinfunction "GPIO41_A8") (pintype "bidirectional"))
    )
    (net (code "61") (name "~{D3{slash}A6}") (class "Default")
      (node (ref "J3") (pin "10") (pinfunction "10_10") (pintype "passive"))
      (node (ref "U3") (pin "E7") (pinfunction "GPIO31_E7") (pintype "bidirectional"))
    )
    (net (code "62") (name "~{D4}") (class "Default")
      (node (ref "J3") (pin "9") (pinfunction "9_9") (pintype "passive"))
      (node (ref "U3") (pin "E1") (pinfunction "GPIO10_E1") (pintype "bidirectional"))
    )
    (net (code "63") (name "~{D5}") (class "Default")
      (node (ref "J3") (pin "8") (pinfunction "8_8") (pintype "passive"))
      (node (ref "U3") (pin "D2") (pinfunction "GPIO30_D2") (pintype "bidirectional"))
    )
    (net (code "64") (name "~{D6}") (class "Default")
      (node (ref "J3") (pin "7") (pinfunction "7_7") (pintype "passive"))
      (node (ref "U3") (pin "F2") (pinfunction "GPIO37_F2") (pintype "bidirectional"))
    )
    (net (code "65") (name "~{D7}") (class "Default")
      (node (ref "J3") (pin "6") (pinfunction "6_6") (pintype "passive"))
      (node (ref "U3") (pin "E3") (pinfunction "GPIO24_E3") (pintype "bidirectional"))
    )
    (net (code "66") (name "~{D8}") (class "Default")
      (node (ref "J3") (pin "5") (pinfunction "5_5") (pintype "passive"))
      (node (ref "U3") (pin "G4") (pinfunction "GPIO46_G4") (pintype "bidirectional"))
    )
    (net (code "67") (name "~{D9{slash}A7}") (class "Default")
      (node (ref "J2") (pin "6") (pinfunction "SWO_6") (pintype "bidirectional"))
      (node (ref "J3") (pin "4") (pinfunction "4_4") (pintype "passive"))
      (node (ref "U3") (pin "F8") (pinfunction "GPIO33_F8") (pintype "bidirectional"))
    )
    (net (code "68") (name "~{D11{slash}MOSI}") (class "Default")
      (node (ref "J4") (pin "12") (pinfunction "12_12") (pintype "passive"))
      (node (ref "U3") (pin "H9") (pinfunction "GPIO28_H9") (pintype "bidirectional"))
    )
    (net (code "69") (name "~{D12{slash}MISO}") (class "Default")
      (node (ref "J4") (pin "13") (pinfunction "13_13") (pintype "passive"))
      (node (ref "U3") (pin "G3") (pinfunction "GPIO25_G3") (pintype "bidirectional"))
    )
    (net (code "70") (name "~{D13{slash}SCK}") (class "Default")
      (node (ref "J4") (pin "11") (pinfunction "11_11") (pintype "passive"))
      (node (ref "U3") (pin "J8") (pinfunction "GPIO27_J8") (pintype "bidirectional"))
    )
    (net (code "71") (name "~{D15{slash}QWIIC_SCL}") (class "Default")
      (node (ref "J6") (pin "4") (pinfunction "4_4") (pintype "passive"))
      (node (ref "TP4") (pin "P$1") (pinfunction "1_P$1") (pintype "bidirectional"))
      (node (ref "U3") (pin "J5") (pinfunction "GPIO5_J5") (pintype "bidirectional"))
    )
    (net (code "72") (name "~{D16{slash}SDA1}") (class "Default")
      (node (ref "J3") (pin "12") (pinfunction "12_12") (pintype "passive"))
      (node (ref "U3") (pin "E2") (pinfunction "GPIO9_E2") (pintype "bidirectional"))
    )
    (net (code "73") (name "~{D17{slash}SCL1}") (class "Default")
      (node (ref "J3") (pin "11") (pinfunction "11_11") (pintype "passive"))
      (node (ref "U3") (pin "F1") (pinfunction "GPIO8_F1") (pintype "bidirectional"))
    )
    (net (code "74") (name "~{D18{slash}LED}") (class "Default")
      (node (ref "R12") (pin "2") (pinfunction "2_2") (pintype "passive"))
      (node (ref "U3") (pin "F3") (pinfunction "GPIO26_F3") (pintype "bidirectional"))
    )
    (net (code "75") (name "~{D19{slash}A0}") (class "Default")
      (node (ref "J4") (pin "5") (pinfunction "5_5") (pintype "passive"))
      (node (ref "U3") (pin "G8") (pinfunction "GPIO13_G8") (pintype "bidirectional"))
    )
    (net (code "76") (name "~{D20{slash}A1}") (class "Default")
      (node (ref "J4") (pin "6") (pinfunction "6_6") (pintype "passive"))
      (node (ref "U3") (pin "G9") (pinfunction "GPIO12_G9") (pintype "bidirectional"))
    )
    (net (code "77") (name "~{D21{slash}A2}") (class "Default")
      (node (ref "J4") (pin "7") (pinfunction "7_7") (pintype "passive"))
      (node (ref "U3") (pin "G6") (pinfunction "GPIO32_G6") (pintype "bidirectional"))
    )
    (net (code "78") (name "~{D22{slash}A3}") (class "Default")
      (node (ref "J4") (pin "8") (pinfunction "8_8") (pintype "passive"))
      (node (ref "U3") (pin "F7") (pinfunction "GPIO35_F7") (pintype "bidirectional"))
    )
    (net (code "79") (name "~{D23{slash}A4}") (class "Default")
      (node (ref "J4") (pin "9") (pinfunction "9_9") (pintype "passive"))
      (node (ref "U3") (pin "E8") (pinfunction "GPIO34_E8") (pintype "bidirectional"))
    )
    (net (code "80") (name "~{D24{slash}A5}") (class "Default")
      (node (ref "J4") (pin "10") (pinfunction "10_10") (pintype "passive"))
      (node (ref "U3") (pin "B9") (pinfunction "GPIO11_B9") (pintype "bidirectional"))
    )
    (net (code "81") (name "~{RESET}") (class "Default")
      (node (ref "C1") (pin "2") (pinfunction "2_2") (pintype "passive"))
      (node (ref "C15") (pin "1") (pinfunction "1_1") (pintype "passive"))
      (node (ref "J2") (pin "10") (pinfunction "~{RESET}_10") (pintype "bidirectional"))
      (node (ref "J4") (pin "1") (pinfunction "1_1") (pintype "passive"))
      (node (ref "R11") (pin "1") (pinfunction "1_1") (pintype "passive"))
      (node (ref "S1") (pin "3") (pinfunction "2_3") (pintype "passive"))
      (node (ref "S1") (pin "4") (pinfunction "2_4") (pintype "passive"))
      (node (ref "U3") (pin "C1") (pinfunction "NRESET_C1") (pintype "bidirectional"))
    )
    (net (code "82") (name "~{RTS}") (class "Default")
      (node (ref "RTS") (pin "1") (pinfunction "1_1") (pintype "passive"))
      (node (ref "U4") (pin "4") (pinfunction "~{RTS}_4") (pintype "bidirectional"))
    )
  )
)
